# PT-100_Amplifier.net
KiCad netlist of a schematic drawn in Altium Designer
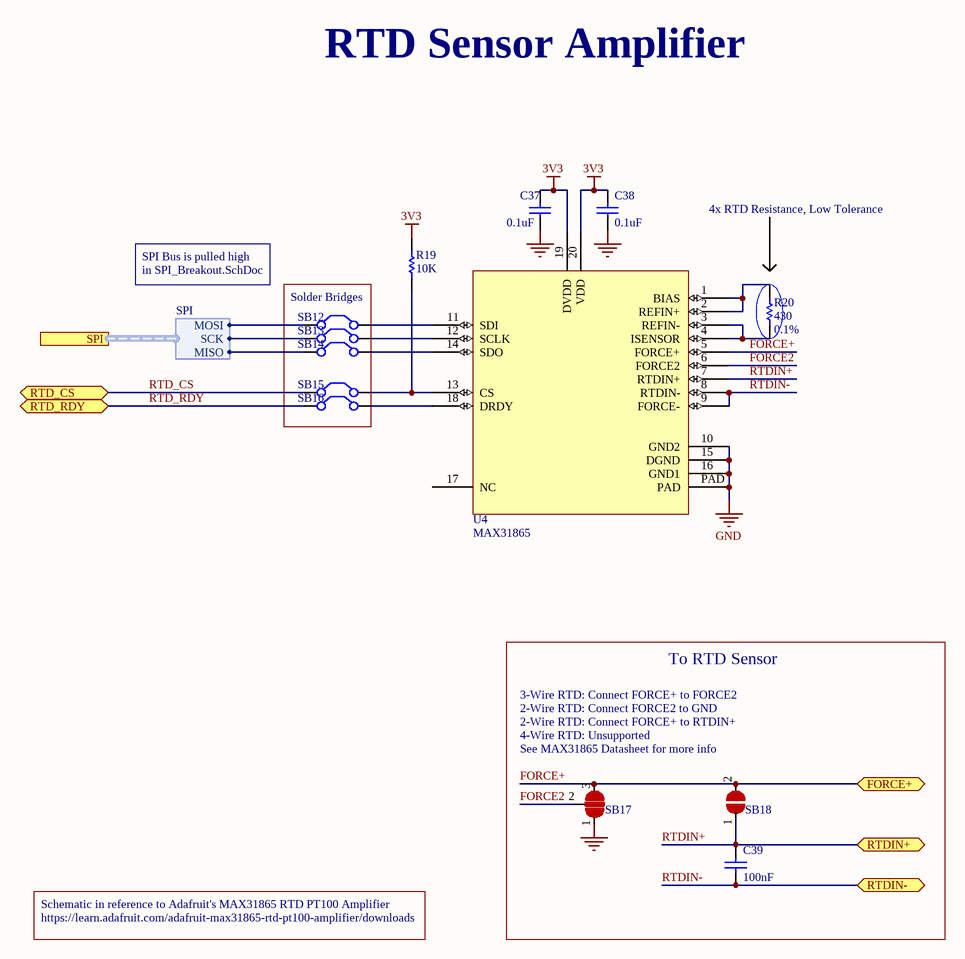
[diagram p0: PT-100_Amplifier.SchDoc]

(export (version "E")
  (design (tool "Eeschema 10.0.6"))
  (components
    (comp (ref "C37")
      (value "0.1uF")
      (footprint "0402")
      (description "Capacitor")
      (fields (field (name "Comment") "Cap"))
      (libsource (lib "Miscellaneous Devices") (part "Cap"))
    )
    (comp (ref "C38")
      (value "0.1uF")
      (footprint "0402")
      (description "Capacitor")
      (fields (field (name "Comment") "Cap"))
      (libsource (lib "Miscellaneous Devices") (part "Cap"))
    )
    (comp (ref "C39")
      (value "100nF")
      (footprint "0402")
      (description "Capacitor")
      (fields (field (name "Comment") "Cap"))
      (libsource (lib "Miscellaneous Devices") (part "Cap"))
    )
    (comp (ref "R19")
      (value "10K")
      (footprint "0402")
      (description "Resistor")
      (fields (field (name "Comment") "Res1"))
      (libsource (lib "Miscellaneous Devices") (part "Res1"))
    )
    (comp (ref "R20")
      (value "430")
      (footprint "0402")
      (description "Resistor")
      (fields (field (name "TOLERANCE") "0.1%") (field (name "Comment") "Res1"))
      (libsource (lib "Miscellaneous Devices") (part "Res1"))
    )
    (comp (ref "SB12")
      (value "Jumper")
      (footprint "SB-2pos")
      (description "Jumper Wire")
      (libsource (lib "Miscellaneous Devices") (part "Jumper"))
    )
    (comp (ref "SB13")
      (value "Jumper")
      (footprint "SB-2pos")
      (description "Jumper Wire")
      (libsource (lib "Miscellaneous Devices") (part "Jumper"))
    )
    (comp (ref "SB14")
      (value "Jumper")
      (footprint "SB-2pos")
      (description "Jumper Wire")
      (libsource (lib "Miscellaneous Devices") (part "Jumper"))
    )
    (comp (ref "SB15")
      (value "Jumper")
      (footprint "SB-2pos")
      (description "Jumper Wire")
      (libsource (lib "Miscellaneous Devices") (part "Jumper"))
    )
    (comp (ref "SB16")
      (value "Jumper")
      (footprint "SB-2pos")
      (description "Jumper Wire")
      (libsource (lib "Miscellaneous Devices") (part "Jumper"))
    )
    (comp (ref "SB17")
      (value "Solder Jumper 3-Way")
      (footprint "SB-3pos")
      (libsource (lib "LaunchyRIOComponents") (part "Solder Jumper 3-Way"))
    )
    (comp (ref "SB18")
      (value "Solder Jumper")
      (footprint "SB-2pos")
      (libsource (lib "LaunchyRIOComponents") (part "Solder Jumper"))
    )
    (comp (ref "U4")
      (value "MAX31865")
      (footprint "TQFN20-EP-Maxim")
      (description "RTD Digital Converter")
      (fields
        (field (name "DIGIKEY PART NUMBER") "MAX31865ATP+-ND")
        (field (name "MANUFACTURER PART NUMBER") "MAX31865ATP+")
      )
      (libsource (lib "LaunchyRIOComponents") (part "MAX31865"))
    )
  )
  (nets
    (net (code "2") (name "/FORCE+") (class "Default")
      (node (ref "SB17") (pin "3") (pinfunction "3_3") (pintype "passive"))
      (node (ref "SB18") (pin "2") (pinfunction "2_2") (pintype "passive"))
      (node (ref "U4") (pin "5") (pinfunction "FORCE+_5") (pintype "bidirectional"))
    )
    (net (code "3") (name "/FORCE2") (class "Default")
      (node (ref "SB17") (pin "2") (pinfunction "2_2") (pintype "passive"))
      (node (ref "U4") (pin "6") (pinfunction "FORCE2_6") (pintype "bidirectional"))
    )
    (net (code "4") (name "/MISO") (class "Default")
      (node (ref "SB14") (pin "1") (pinfunction "C1_1") (pintype "passive"))
    )
    (net (code "5") (name "/MOSI") (class "Default")
      (node (ref "SB12") (pin "1") (pinfunction "C1_1") (pintype "passive"))
    )
    (net (code "6") (name "/RTDIN+") (class "Default")
      (node (ref "C39") (pin "2") (pinfunction "2_2") (pintype "passive"))
      (node (ref "SB18") (pin "1") (pinfunction "1_1") (pintype "passive"))
      (node (ref "U4") (pin "7") (pinfunction "RTDIN+_7") (pintype "bidirectional"))
    )
    (net (code "7") (name "/RTDIN-") (class "Default")
      (node (ref "C39") (pin "1") (pinfunction "1_1") (pintype "passive"))
      (node (ref "U4") (pin "8") (pinfunction "RTDIN-_8") (pintype "bidirectional"))
      (node (ref "U4") (pin "9") (pinfunction "FORCE-_9") (pintype "bidirectional"))
    )
    (net (code "8") (name "/RTD_CS") (class "Default")
      (node (ref "SB15") (pin "1") (pinfunction "C1_1") (pintype "passive"))
    )
    (net (code "9") (name "/RTD_RDY") (class "Default")
      (node (ref "SB16") (pin "1") (pinfunction "C1_1") (pintype "passive"))
    )
    (net (code "10") (name "/SCK") (class "Default")
      (node (ref "SB13") (pin "1") (pinfunction "C1_1") (pintype "passive"))
    )
    (net (code "12") (name "3V3") (class "Default")
      (node (ref "C37") (pin "2") (pinfunction "2_2") (pintype "passive"))
      (node (ref "C38") (pin "2") (pinfunction "2_2") (pintype "passive"))
      (node (ref "R19") (pin "1") (pinfunction "1_1") (pintype "passive"))
      (node (ref "U4") (pin "19") (pinfunction "DVDD_19") (pintype "power_in"))
      (node (ref "U4") (pin "20") (pinfunction "VDD_20") (pintype "power_in"))
    )
    (net (code "13") (name "GND") (class "Default")
      (node (ref "C37") (pin "1") (pinfunction "1_1") (pintype "passive"))
      (node (ref "C38") (pin "1") (pinfunction "1_1") (pintype "passive"))
      (node (ref "SB17") (pin "1") (pinfunction "3_1") (pintype "passive"))
      (node (ref "U4") (pin "10") (pinfunction "GND2_10") (pintype "power_in"))
      (node (ref "U4") (pin "15") (pinfunction "DGND_15") (pintype "power_in"))
      (node (ref "U4") (pin "16") (pinfunction "GND1_16") (pintype "power_in"))
      (node (ref "U4") (pin "PAD") (pinfunction "PAD_PAD") (pintype "power_in"))
    )
    (net (code "14") (name "Net-(SB12-C2)") (class "Default")
      (node (ref "SB12") (pin "2") (pinfunction "C2_2") (pintype "passive"))
      (node (ref "U4") (pin "11") (pinfunction "SDI_11") (pintype "bidirectional"))
    )
    (net (code "15") (name "Net-(SB13-C2)") (class "Default")
      (node (ref "SB13") (pin "2") (pinfunction "C2_2") (pintype "passive"))
      (node (ref "U4") (pin "12") (pinfunction "SCLK_12") (pintype "bidirectional"))
    )
    (net (code "16") (name "Net-(SB14-C2)") (class "Default")
      (node (ref "SB14") (pin "2") (pinfunction "C2_2") (pintype "passive"))
      (node (ref "U4") (pin "14") (pinfunction "SDO_14") (pintype "bidirectional"))
    )
    (net (code "17") (name "Net-(SB15-C2)") (class "Default")
      (node (ref "R19") (pin "2") (pinfunction "2_2") (pintype "passive"))
      (node (ref "SB15") (pin "2") (pinfunction "C2_2") (pintype "passive"))
      (node (ref "U4") (pin "13") (pinfunction "CS_13") (pintype "bidirectional"))
    )
    (net (code "18") (name "Net-(SB16-C2)") (class "Default")
      (node (ref "SB16") (pin "2") (pinfunction "C2_2") (pintype "passive"))
      (node (ref "U4") (pin "18") (pinfunction "DRDY_18") (pintype "bidirectional"))
    )
    (net (code "19") (name "Net-(U4-BIAS)") (class "Default")
      (node (ref "R20") (pin "1") (pinfunction "1_1") (pintype "passive"))
      (node (ref "U4") (pin "1") (pinfunction "BIAS_1") (pintype "bidirectional"))
      (node (ref "U4") (pin "2") (pinfunction "REFIN+_2") (pintype "bidirectional"))
    )
    (net (code "20") (name "Net-(U4-ISENSOR)") (class "Default")
      (node (ref "R20") (pin "2") (pinfunction "2_2") (pintype "passive"))
      (node (ref "U4") (pin "3") (pinfunction "REFIN-_3") (pintype "bidirectional"))
      (node (ref "U4") (pin "4") (pinfunction "ISENSOR_4") (pintype "bidirectional"))
    )
    (net (code "21") (name "unconnected-(U4-NC-Pad17)") (class "Default")
      (node (ref "U4") (pin "17") (pinfunction "NC_17") (pintype "passive"))
    )
  )
)
